# Driver_LED.net
KiCad netlist of a schematic drawn in Altium Designer
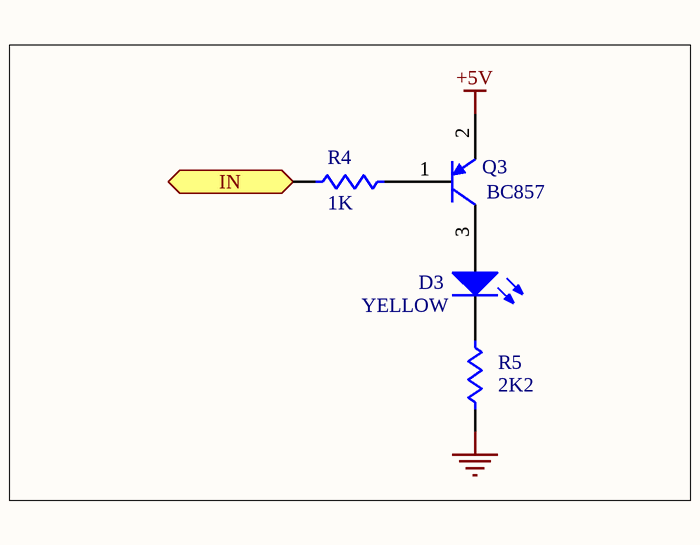
[diagram p0: Driver_LED.SchDoc]

(export (version "E")
  (design (tool "Eeschema 10.0.6"))
  (components
    (comp (ref "D3")
      (value "YELLOW")
      (footprint "0805_Diode")
      (description "Typical INFRARED GaAs LED")
      (fields (field (name "MANUFACTURER") "Generic Components") (field (name "PUBLISHER") "Altium Limited"))
      (libsource (lib "my Libraries") (part "Optical Transmitter"))
    )
    (comp (ref "Q3")
      (value "BC857")
      (footprint "SOT23-3N")
      (description "Silicon Bipolar Transistor")
      (libsource (lib "my Libraries") (part "BC857"))
    )
    (comp (ref "R4")
      (value "1K")
      (footprint "0805")
      (description "Resistor")
      (fields (field (name "MANUFACTURER") "Generic Components") (field (name "PUBLISHER") "Altium Limited"))
      (libsource (lib "Miscellaneous Devices") (part "Res1"))
    )
    (comp (ref "R5")
      (value "2K2")
      (footprint "0805")
      (description "Resistor")
      (fields (field (name "MANUFACTURER") "Generic Components") (field (name "PUBLISHER") "Altium Limited"))
      (libsource (lib "Miscellaneous Devices") (part "Res1"))
    )
  )
  (nets
    (net (code "1") (name "+5V") (class "Default")
      (node (ref "Q3") (pin "2") (pinfunction "E_2") (pintype "passive"))
    )
    (net (code "2") (name "/IN") (class "Default")
      (node (ref "R4") (pin "2") (pinfunction "2_2") (pintype "passive"))
    )
    (net (code "3") (name "GND") (class "Default")
      (node (ref "R5") (pin "1") (pinfunction "1_1") (pintype "passive"))
    )
    (net (code "4") (name "Net-(D3-A)") (class "Default")
      (node (ref "D3") (pin "1") (pinfunction "A_1") (pintype "passive"))
      (node (ref "Q3") (pin "3") (pinfunction "C_3") (pintype "passive"))
    )
    (net (code "5") (name "Net-(D3-K)") (class "Default")
      (node (ref "D3") (pin "2") (pinfunction "K_2") (pintype "passive"))
      (node (ref "R5") (pin "2") (pinfunction "2_2") (pintype "passive"))
    )
    (net (code "6") (name "Net-(Q3-B)") (class "Default")
      (node (ref "Q3") (pin "1") (pinfunction "B_1") (pintype "passive"))
      (node (ref "R4") (pin "1") (pinfunction "1_1") (pintype "passive"))
    )
  )
)
